# SCH_-_Wireless_Coms.net
KiCad netlist of a schematic drawn in Altium Designer
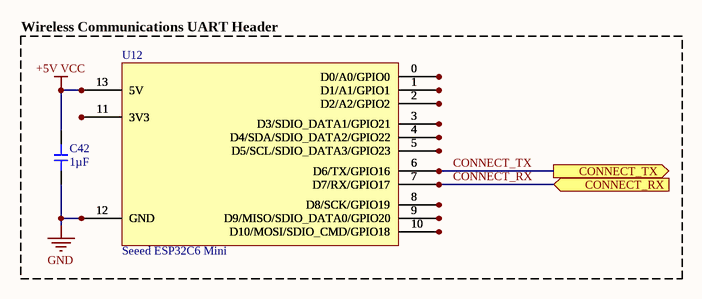
[diagram p0: SCH - Wireless Coms.SchDoc]

(export (version "E")
  (design (tool "Eeschema 10.0.6"))
  (components
    (comp (ref "C42")
      (value "1µF")
      (footprint "CAP-0402")
      (description "Capacitor, Ceramic (MLCC), 1uF, ±10%, 25V, X5R, ±10%, SMD 0402")
      (fields
        (field (name "MANUFACTURER PART NUMBER") "CL05A105KA5NQNC")
        (field (name "MANUFACTURER") "Samsung Electro-Mechanics")
      )
      (libsource (lib "Finmac Systems") (part "GRM21BR61H106KE43L"))
    )
    (comp (ref "U12")
      (value "Seeed ESP32C6 Mini")
      (footprint "ESP32C6 Mini")
      (libsource (lib "qfuse_sch_lib") (part "ESP32C6 Mini"))
    )
  )
  (nets
    (net (code "1") (name "+5V VCC") (class "Default")
      (node (ref "C42") (pin "2") (pinfunction "2_2") (pintype "passive"))
      (node (ref "U12") (pin "13") (pinfunction "5V_13") (pintype "passive"))
    )
    (net (code "2") (name "/CONNECT_RX") (class "Default")
      (node (ref "U12") (pin "7") (pinfunction "D7/RX/GPIO17_7") (pintype "passive"))
    )
    (net (code "3") (name "/CONNECT_TX") (class "Default")
      (node (ref "U12") (pin "6") (pinfunction "D6/TX/GPIO16_6") (pintype "passive"))
    )
    (net (code "4") (name "GND") (class "Default")
      (node (ref "C42") (pin "1") (pinfunction "1_1") (pintype "passive"))
      (node (ref "U12") (pin "12") (pinfunction "GND_12") (pintype "passive"))
    )
    (net (code "5") (name "Net-(U12-3V3)") (class "Default")
      (node (ref "U12") (pin "11") (pinfunction "3V3_11") (pintype "passive"))
    )
    (net (code "6") (name "Net-(U12-D0{slash}A0{slash}GPIO0)") (class "Default")
      (node (ref "U12") (pin "0") (pinfunction "D0/A0/GPIO0_0") (pintype "passive"))
    )
    (net (code "7") (name "Net-(U12-D1{slash}A1{slash}GPIO1)") (class "Default")
      (node (ref "U12") (pin "1") (pinfunction "D1/A1/GPIO1_1") (pintype "passive"))
    )
    (net (code "8") (name "Net-(U12-D2{slash}A2{slash}GPIO2)") (class "Default")
      (node (ref "U12") (pin "2") (pinfunction "D2/A2/GPIO2_2") (pintype "passive"))
    )
    (net (code "9") (name "Net-(U12-D3{slash}SDIO_DATA1{slash}GPIO21)") (class "Default")
      (node (ref "U12") (pin "3") (pinfunction "D3/SDIO_DATA1/GPIO21_3") (pintype "passive"))
    )
    (net (code "10") (name "Net-(U12-D4{slash}SDA{slash}SDIO_DATA2{slash}GPIO22)") (class "Default")
      (node (ref "U12") (pin "4") (pinfunction "D4/SDA/SDIO_DATA2/GPIO22_4") (pintype "passive"))
    )
    (net (code "11") (name "Net-(U12-D5{slash}SCL{slash}SDIO_DATA3{slash}GPIO23)") (class "Default")
      (node (ref "U12") (pin "5") (pinfunction "D5/SCL/SDIO_DATA3/GPIO23_5") (pintype "passive"))
    )
    (net (code "12") (name "Net-(U12-D8{slash}SCK{slash}GPIO19)") (class "Default")
      (node (ref "U12") (pin "8") (pinfunction "D8/SCK/GPIO19_8") (pintype "passive"))
    )
    (net (code "13") (name "Net-(U12-D9{slash}MISO{slash}SDIO_DATA0{slash}GPIO20)") (class "Default")
      (node (ref "U12") (pin "9") (pinfunction "D9/MISO/SDIO_DATA0/GPIO20_9") (pintype "passive"))
    )
    (net (code "14") (name "Net-(U12-D10{slash}MOSI{slash}SDIO_CMD{slash}GPIO18)") (class "Default")
      (node (ref "U12") (pin "10") (pinfunction "D10/MOSI/SDIO_CMD/GPIO18_10") (pintype "passive"))
    )
  )
)
